# K-Diag_small-_double.net
KiCad netlist of a schematic drawn in EAGLE
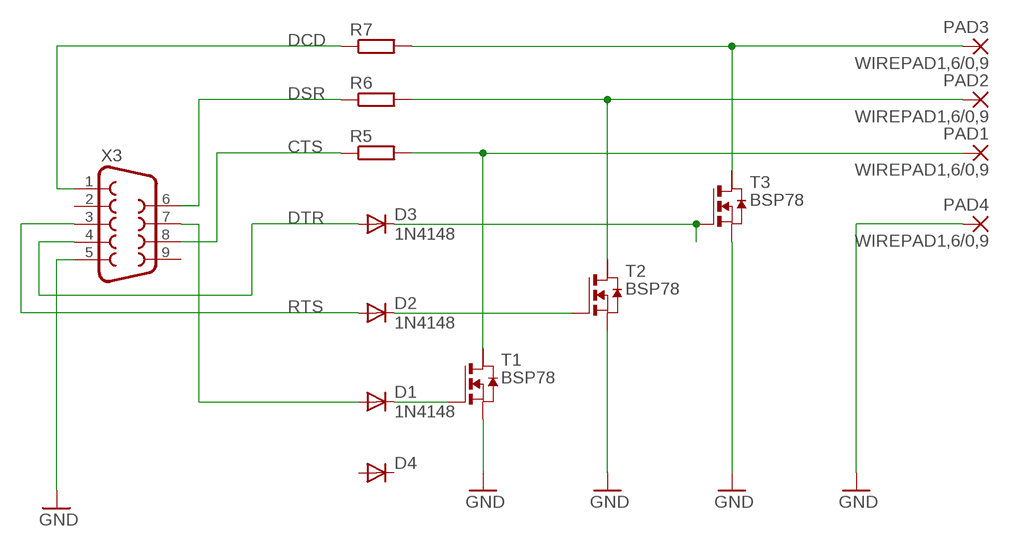
[diagram p0: schematic, sheet 1]

(export (version "E")
  (design (tool "Eeschema 10.0.6"))
  (components
    (comp (ref "D1")
      (value "1N4148")
      (footprint "eagle-import:SOD323-W")
      (libsource (lib "eagle-import") (part "DIODE-SOD323-W"))
    )
    (comp (ref "D2")
      (value "1N4148")
      (footprint "eagle-import:SOD323-W")
      (libsource (lib "eagle-import") (part "DIODE-SOD323-W"))
    )
    (comp (ref "D3")
      (value "1N4148")
      (footprint "eagle-import:SOD323-W")
      (libsource (lib "eagle-import") (part "DIODE-SOD323-W"))
    )
    (comp (ref "D4")
      (value "DIODE-SOD323-W")
      (footprint "eagle-import:SOD323-W")
      (libsource (lib "eagle-import") (part "DIODE-SOD323-W"))
    )
    (comp (ref "PAD1")
      (value "WIREPAD1,6/0,9")
      (footprint "eagle-import:1,6_0,9")
      (libsource (lib "eagle-import") (part "WIREPAD1,6/0,9"))
    )
    (comp (ref "PAD2")
      (value "WIREPAD1,6/0,9")
      (footprint "eagle-import:1,6_0,9")
      (libsource (lib "eagle-import") (part "WIREPAD1,6/0,9"))
    )
    (comp (ref "PAD3")
      (value "WIREPAD1,6/0,9")
      (footprint "eagle-import:1,6_0,9")
      (libsource (lib "eagle-import") (part "WIREPAD1,6/0,9"))
    )
    (comp (ref "PAD4")
      (value "WIREPAD1,6/0,9")
      (footprint "eagle-import:1,6_0,9")
      (libsource (lib "eagle-import") (part "WIREPAD1,6/0,9"))
    )
    (comp (ref "R5")
      (value "R-EU_R0805")
      (footprint "eagle-import:R0805")
      (libsource (lib "eagle-import") (part "R-EU_R0805"))
    )
    (comp (ref "R6")
      (value "R-EU_R0805")
      (footprint "eagle-import:R0805")
      (libsource (lib "eagle-import") (part "R-EU_R0805"))
    )
    (comp (ref "R7")
      (value "R-EU_R0805")
      (footprint "eagle-import:R0805")
      (libsource (lib "eagle-import") (part "R-EU_R0805"))
    )
    (comp (ref "T1")
      (value "BSP78")
      (footprint "eagle-import:SOT223")
      (libsource (lib "eagle-import") (part "NMOSSOT223"))
    )
    (comp (ref "T2")
      (value "BSP78")
      (footprint "eagle-import:SOT223")
      (libsource (lib "eagle-import") (part "NMOSSOT223"))
    )
    (comp (ref "T3")
      (value "BSP78")
      (footprint "eagle-import:SOT223")
      (libsource (lib "eagle-import") (part "NMOSSOT223"))
    )
    (comp (ref "X3")
      (value "F09D")
      (footprint "eagle-import:F09D")
      (libsource (lib "eagle-import") (part "F09D"))
    )
  )
  (nets
    (net (code "1") (name "/CTS") (class "Default")
      (node (ref "R5") (pin "1") (pinfunction "1_1") (pintype "passive"))
      (node (ref "X3") (pin "8") (pinfunction "8_8") (pintype "passive"))
    )
    (net (code "2") (name "/DCD") (class "Default")
      (node (ref "R7") (pin "1") (pinfunction "1_1") (pintype "passive"))
      (node (ref "X3") (pin "1") (pinfunction "1_1") (pintype "passive"))
    )
    (net (code "3") (name "/DSR") (class "Default")
      (node (ref "R6") (pin "1") (pinfunction "1_1") (pintype "passive"))
      (node (ref "X3") (pin "6") (pinfunction "6_6") (pintype "passive"))
    )
    (net (code "4") (name "/DTR") (class "Default")
      (node (ref "D3") (pin "A") (pinfunction "A_A") (pintype "passive"))
      (node (ref "X3") (pin "4") (pinfunction "4_4") (pintype "passive"))
    )
    (net (code "5") (name "/RTS") (class "Default")
      (node (ref "D2") (pin "A") (pinfunction "A_A") (pintype "passive"))
      (node (ref "X3") (pin "3") (pinfunction "3_3") (pintype "passive"))
    )
    (net (code "6") (name "GND") (class "Default")
      (node (ref "PAD4") (pin "1") (pinfunction "P_1") (pintype "passive"))
      (node (ref "T1") (pin "3") (pinfunction "S_3") (pintype "passive"))
      (node (ref "T2") (pin "3") (pinfunction "S_3") (pintype "passive"))
      (node (ref "T3") (pin "3") (pinfunction "S_3") (pintype "passive"))
      (node (ref "X3") (pin "5") (pinfunction "5_5") (pintype "passive"))
    )
    (net (code "7") (name "Net-(D1-PadA)") (class "Default")
      (node (ref "D1") (pin "A") (pinfunction "A_A") (pintype "passive"))
      (node (ref "X3") (pin "7") (pinfunction "7_7") (pintype "passive"))
    )
    (net (code "8") (name "Net-(PAD1-P)") (class "Default")
      (node (ref "PAD1") (pin "1") (pinfunction "P_1") (pintype "passive"))
      (node (ref "R5") (pin "2") (pinfunction "2_2") (pintype "passive"))
      (node (ref "T1") (pin "2") (pinfunction "D_2") (pintype "passive"))
    )
    (net (code "9") (name "Net-(PAD2-P)") (class "Default")
      (node (ref "PAD2") (pin "1") (pinfunction "P_1") (pintype "passive"))
      (node (ref "R6") (pin "2") (pinfunction "2_2") (pintype "passive"))
      (node (ref "T2") (pin "2") (pinfunction "D_2") (pintype "passive"))
    )
    (net (code "10") (name "Net-(PAD3-P)") (class "Default")
      (node (ref "PAD3") (pin "1") (pinfunction "P_1") (pintype "passive"))
      (node (ref "R7") (pin "2") (pinfunction "2_2") (pintype "passive"))
      (node (ref "T3") (pin "2") (pinfunction "D_2") (pintype "passive"))
    )
    (net (code "11") (name "Net-(T1-G)") (class "Default")
      (node (ref "D1") (pin "C") (pinfunction "C_C") (pintype "passive"))
      (node (ref "T1") (pin "1") (pinfunction "G_1") (pintype "passive"))
    )
    (net (code "12") (name "Net-(T2-G)") (class "Default")
      (node (ref "D2") (pin "C") (pinfunction "C_C") (pintype "passive"))
      (node (ref "T2") (pin "1") (pinfunction "G_1") (pintype "passive"))
    )
    (net (code "13") (name "Net-(T3-G)") (class "Default")
      (node (ref "D3") (pin "C") (pinfunction "C_C") (pintype "passive"))
      (node (ref "T3") (pin "1") (pinfunction "G_1") (pintype "passive"))
    )
    (net (code "14") (name "unconnected-(D4-PadA)") (class "Default")
      (node (ref "D4") (pin "A") (pinfunction "A_A") (pintype "passive"))
    )
    (net (code "15") (name "unconnected-(D4-PadC)") (class "Default")
      (node (ref "D4") (pin "C") (pinfunction "C_C") (pintype "passive"))
    )
    (net (code "16") (name "unconnected-(T1-D2-Pad4)") (class "Default")
      (node (ref "T1") (pin "4") (pinfunction "D2_4") (pintype "passive"))
    )
    (net (code "17") (name "unconnected-(T2-D2-Pad4)") (class "Default")
      (node (ref "T2") (pin "4") (pinfunction "D2_4") (pintype "passive"))
    )
    (net (code "18") (name "unconnected-(T3-D2-Pad4)") (class "Default")
      (node (ref "T3") (pin "4") (pinfunction "D2_4") (pintype "passive"))
    )
    (net (code "19") (name "unconnected-(X3-Pad2)") (class "Default")
      (node (ref "X3") (pin "2") (pinfunction "2_2") (pintype "passive"))
    )
    (net (code "20") (name "unconnected-(X3-Pad9)") (class "Default")
      (node (ref "X3") (pin "9") (pinfunction "9_9") (pintype "passive"))
    )
  )
)
